# HW1_52.net
KiCad netlist of a schematic drawn in EasyEDA
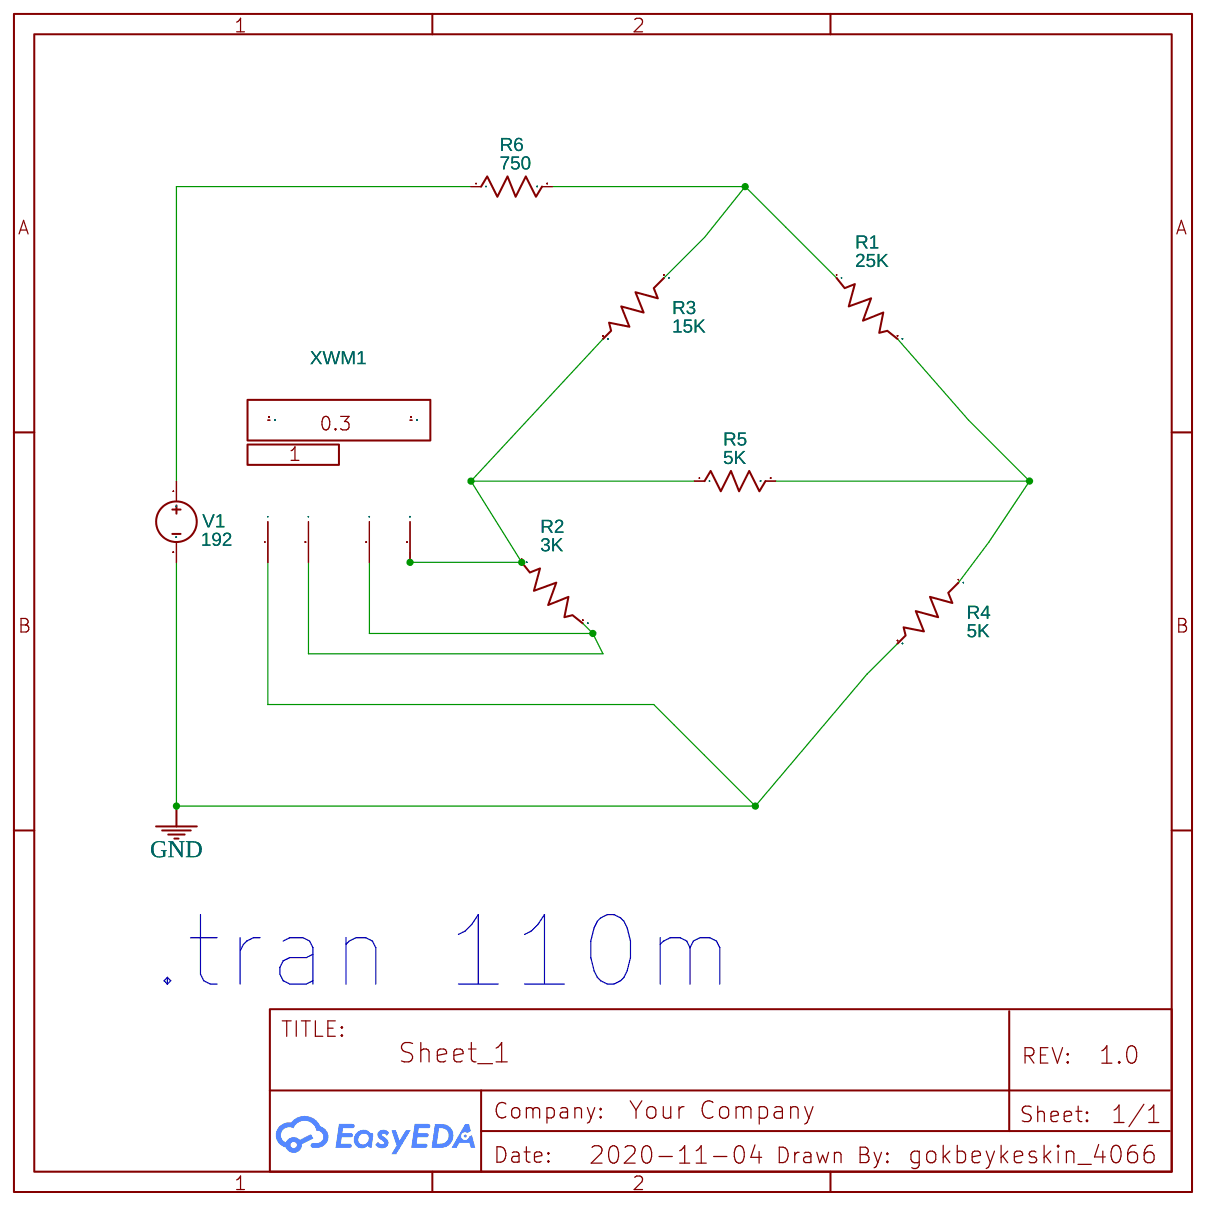
[diagram p0: schematic sheet]

(export (version "E")
  (design (tool "Eeschema 10.0.6"))
  (components
    (comp (ref "R1") (value "25K") (libsource (lib "") (part "Resistor_45Degree_US_1")))
    (comp (ref "R2") (value "3K") (libsource (lib "") (part "Resistor_45Degree_US_1")))
    (comp (ref "R3") (value "15K") (libsource (lib "") (part "Resistor_45Degree_US")))
    (comp (ref "R4") (value "5K") (libsource (lib "") (part "Resistor_45Degree_US")))
    (comp (ref "R5") (value "5K") (libsource (lib "") (part "Resistor_US")))
    (comp (ref "R6") (value "750") (libsource (lib "") (part "Resistor_US")))
    (comp (ref "V1") (value "192") (libsource (lib "") (part "VDC")))
    (comp (ref "XWM1") (value "Wattmeter") (libsource (lib "") (part "WATTMETER")))
  )
  (nets
    (net (code "1") (name "GND") (class "Default")
      (node (ref "R4") (pin "2") (pinfunction "2_2") (pintype "unspecified"))
      (node (ref "V1") (pin "2") (pinfunction "2_2") (pintype "unspecified"))
      (node (ref "XWM1") (pin "4") (pinfunction "I-_4") (pintype "unspecified"))
    )
    (net (code "2") (name "Net-(R1-Pad1)") (class "Default")
      (node (ref "R1") (pin "1") (pinfunction "1_1") (pintype "unspecified"))
      (node (ref "R3") (pin "1") (pinfunction "1_1") (pintype "unspecified"))
      (node (ref "R6") (pin "2") (pinfunction "2_2") (pintype "unspecified"))
    )
    (net (code "3") (name "Net-(R1-Pad2)") (class "Default")
      (node (ref "R1") (pin "2") (pinfunction "2_2") (pintype "unspecified"))
      (node (ref "R4") (pin "1") (pinfunction "1_1") (pintype "unspecified"))
      (node (ref "R5") (pin "2") (pinfunction "2_2") (pintype "unspecified"))
    )
    (net (code "4") (name "Net-(R6-Pad1)") (class "Default")
      (node (ref "R6") (pin "1") (pinfunction "1_1") (pintype "unspecified"))
      (node (ref "V1") (pin "1") (pinfunction "1_1") (pintype "unspecified"))
    )
    (net (code "5") (name "Net-(XWM1-I+)") (class "Default")
      (node (ref "R2") (pin "2") (pinfunction "2_2") (pintype "unspecified"))
      (node (ref "XWM1") (pin "2") (pinfunction "V-_2") (pintype "unspecified"))
      (node (ref "XWM1") (pin "3") (pinfunction "I+_3") (pintype "unspecified"))
    )
    (net (code "6") (name "Net-(XWM1-V+)") (class "Default")
      (node (ref "R2") (pin "1") (pinfunction "1_1") (pintype "unspecified"))
      (node (ref "R3") (pin "2") (pinfunction "2_2") (pintype "unspecified"))
      (node (ref "R5") (pin "1") (pinfunction "1_1") (pintype "unspecified"))
      (node (ref "XWM1") (pin "1") (pinfunction "V+_1") (pintype "unspecified"))
    )
    (net (code "7") (name "unconnected-(XWM1-PadP)") (class "Default")
      (node (ref "XWM1") (pin "P") (pinfunction "P_P") (pintype "unspecified"))
    )
    (net (code "8") (name "unconnected-(XWM1-PadPF)") (class "Default")
      (node (ref "XWM1") (pin "PF") (pinfunction "PF_PF") (pintype "unspecified"))
    )
  )
)
